# devBoard.net
KiCad netlist of a schematic drawn in EAGLE
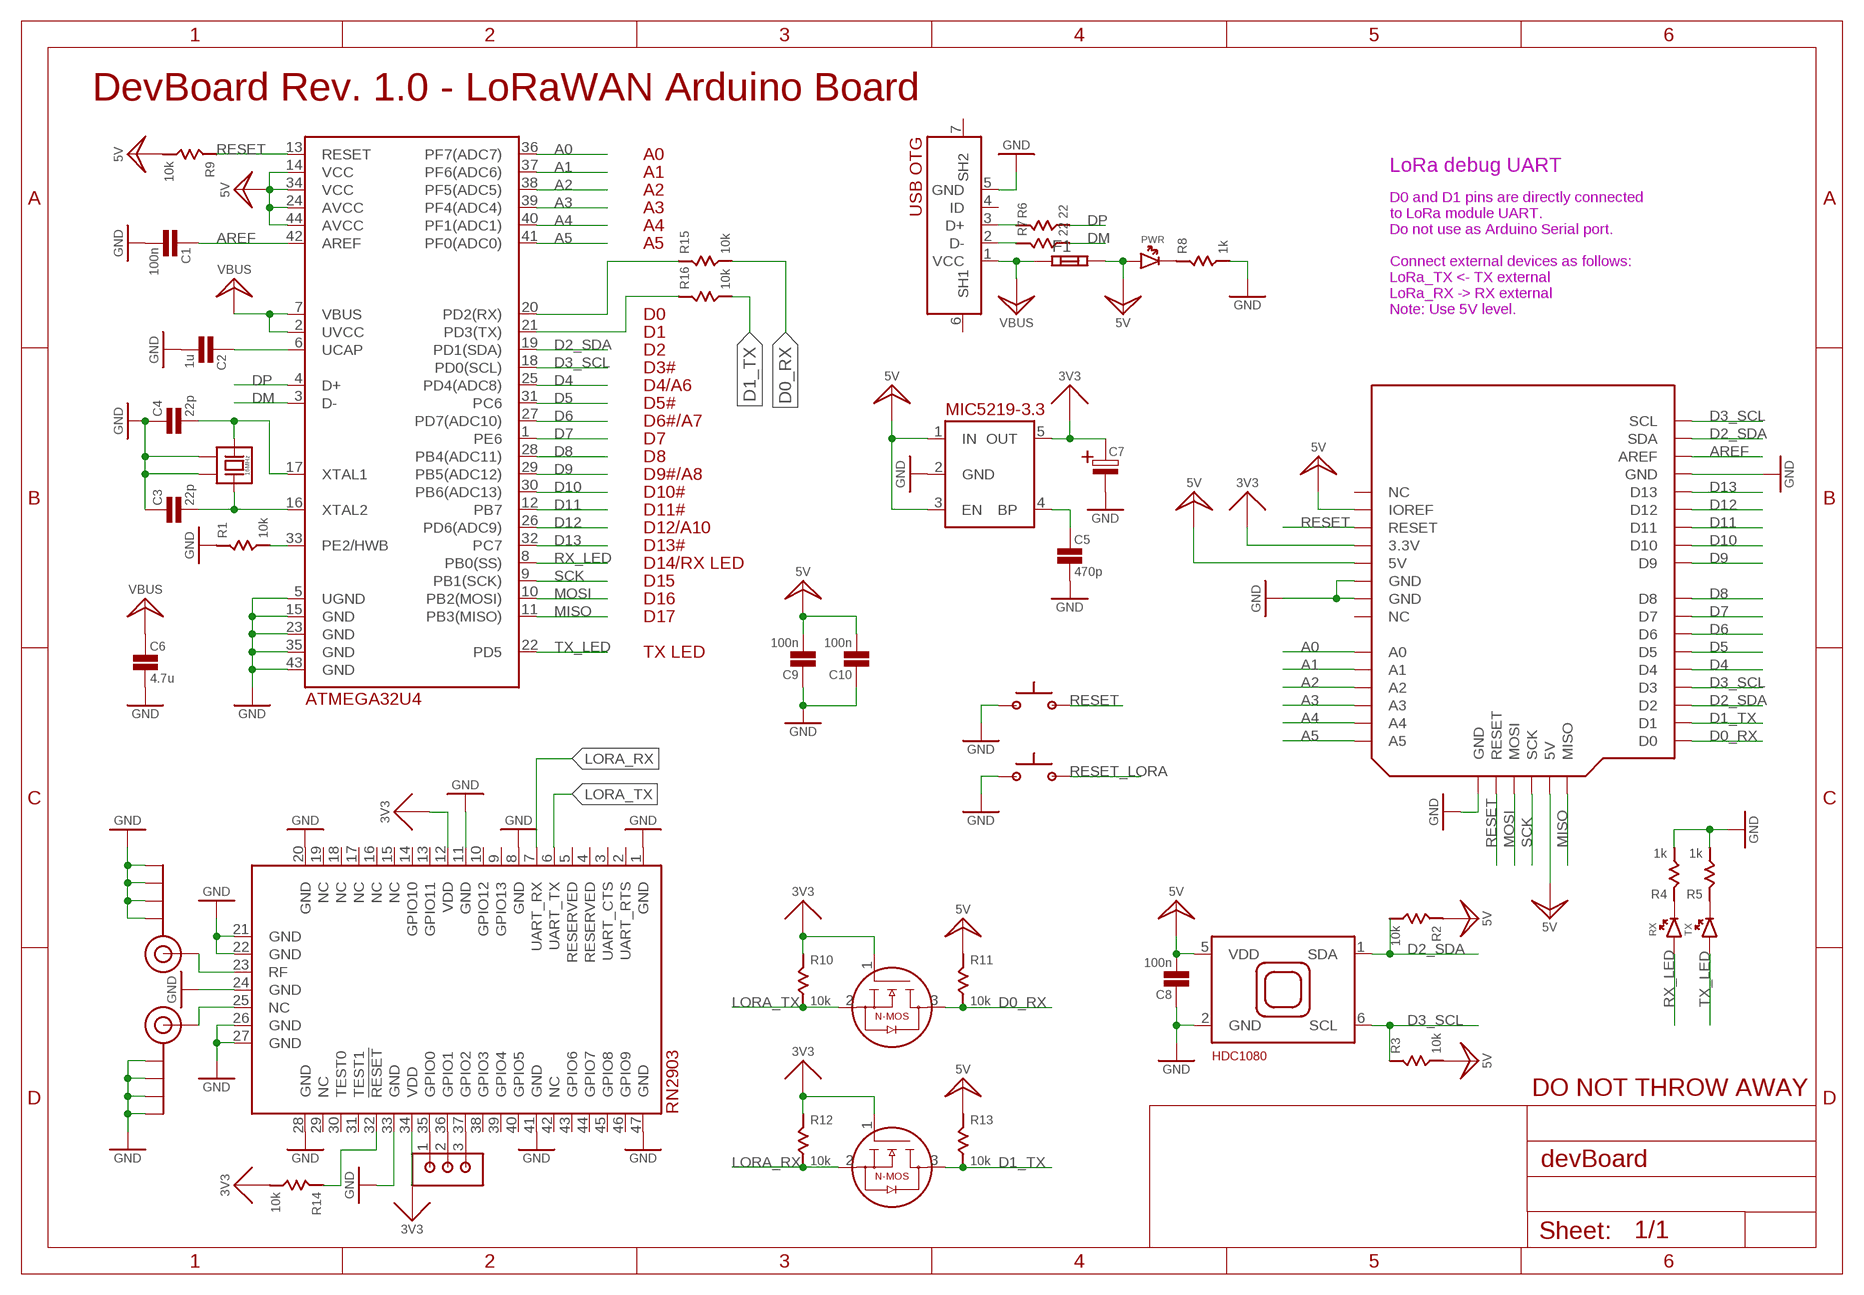
[diagram p0: schematic, sheet 1]

(export (version "E")
  (design (tool "Eeschema 10.0.6"))
  (components
    (comp (ref "C1")
      (value "100n")
      (footprint "eagle-import:0603")
      (libsource (lib "eagle-import") (part "C0603"))
    )
    (comp (ref "C2")
      (value "1u")
      (footprint "eagle-import:0603")
      (libsource (lib "eagle-import") (part "C0603"))
    )
    (comp (ref "C3")
      (value "22p")
      (footprint "eagle-import:0603")
      (libsource (lib "eagle-import") (part "C0603"))
    )
    (comp (ref "C4")
      (value "22p")
      (footprint "eagle-import:0603")
      (libsource (lib "eagle-import") (part "C0603"))
    )
    (comp (ref "C5")
      (value "470p")
      (footprint "eagle-import:0603")
      (libsource (lib "eagle-import") (part "C0603"))
    )
    (comp (ref "C6")
      (value "4.7u")
      (footprint "eagle-import:0603")
      (libsource (lib "eagle-import") (part "C0603"))
    )
    (comp (ref "C7")
      (value "CT3216")
      (footprint "eagle-import:CT3216")
      (libsource (lib "eagle-import") (part "CT3216"))
    )
    (comp (ref "C8")
      (value "100n")
      (footprint "eagle-import:0603")
      (libsource (lib "eagle-import") (part "C0603"))
    )
    (comp (ref "C9")
      (value "100n")
      (footprint "eagle-import:0603")
      (libsource (lib "eagle-import") (part "C0603"))
    )
    (comp (ref "C10")
      (value "100n")
      (footprint "eagle-import:0603")
      (libsource (lib "eagle-import") (part "C0603"))
    )
    (comp (ref "F1")
      (value "MF-MSMF050")
      (footprint "eagle-import:MF-MSMF050")
      (libsource (lib "eagle-import") (part "MF-MSMF050"))
    )
    (comp (ref "J$1")
      (value "SMA_EDGE")
      (footprint "eagle-import:SMA-EDGE")
      (libsource (lib "eagle-import") (part "SMA_EDGE"))
    )
    (comp (ref "J$2")
      (value "SMA_EDGE")
      (footprint "eagle-import:SMA-EDGE")
      (libsource (lib "eagle-import") (part "SMA_EDGE"))
    )
    (comp (ref "PWR")
      (value "PWR")
      (footprint "eagle-import:0603LED")
      (libsource (lib "eagle-import") (part "0603LED"))
    )
    (comp (ref "R1")
      (value "10k")
      (footprint "eagle-import:0603")
      (libsource (lib "eagle-import") (part "R0603"))
    )
    (comp (ref "R2")
      (value "10k")
      (footprint "eagle-import:0603")
      (libsource (lib "eagle-import") (part "R0603"))
    )
    (comp (ref "R3")
      (value "10k")
      (footprint "eagle-import:0603")
      (libsource (lib "eagle-import") (part "R0603"))
    )
    (comp (ref "R4")
      (value "1k")
      (footprint "eagle-import:0603")
      (libsource (lib "eagle-import") (part "R0603"))
    )
    (comp (ref "R5")
      (value "1k")
      (footprint "eagle-import:0603")
      (libsource (lib "eagle-import") (part "R0603"))
    )
    (comp (ref "R6")
      (value "22")
      (footprint "eagle-import:0603")
      (libsource (lib "eagle-import") (part "R0603"))
    )
    (comp (ref "R7")
      (value "22")
      (footprint "eagle-import:0603")
      (libsource (lib "eagle-import") (part "R0603"))
    )
    (comp (ref "R8")
      (value "1k")
      (footprint "eagle-import:0603")
      (libsource (lib "eagle-import") (part "R0603"))
    )
    (comp (ref "R9")
      (value "10k")
      (footprint "eagle-import:0603")
      (libsource (lib "eagle-import") (part "R0603"))
    )
    (comp (ref "R10")
      (value "10k")
      (footprint "eagle-import:0603")
      (libsource (lib "eagle-import") (part "R0603"))
    )
    (comp (ref "R11")
      (value "10k")
      (footprint "eagle-import:0603")
      (libsource (lib "eagle-import") (part "R0603"))
    )
    (comp (ref "R12")
      (value "10k")
      (footprint "eagle-import:0603")
      (libsource (lib "eagle-import") (part "R0603"))
    )
    (comp (ref "R13")
      (value "10k")
      (footprint "eagle-import:0603")
      (libsource (lib "eagle-import") (part "R0603"))
    )
    (comp (ref "R14")
      (value "10k")
      (footprint "eagle-import:0603")
      (libsource (lib "eagle-import") (part "R0603"))
    )
    (comp (ref "R15")
      (value "10k")
      (footprint "eagle-import:0603")
      (libsource (lib "eagle-import") (part "R0603"))
    )
    (comp (ref "R16")
      (value "10k")
      (footprint "eagle-import:0603")
      (libsource (lib "eagle-import") (part "R0603"))
    )
    (comp (ref "RX")
      (value "RX")
      (footprint "eagle-import:0603LED")
      (libsource (lib "eagle-import") (part "0603LED"))
    )
    (comp (ref "SW2")
      (value "PUSH_BTN")
      (footprint "eagle-import:PUSH_BTN")
      (libsource (lib "eagle-import") (part "PUSH_BTN"))
    )
    (comp (ref "SW3")
      (value "PUSH_BTN")
      (footprint "eagle-import:PUSH_BTN")
      (libsource (lib "eagle-import") (part "PUSH_BTN"))
    )
    (comp (ref "T1")
      (value "BSS138")
      (footprint "eagle-import:SOT23-3")
      (libsource (lib "eagle-import") (part "BSS138"))
    )
    (comp (ref "T2")
      (value "BSS138")
      (footprint "eagle-import:SOT23-3")
      (libsource (lib "eagle-import") (part "BSS138"))
    )
    (comp (ref "TX")
      (value "TX")
      (footprint "eagle-import:0603LED")
      (libsource (lib "eagle-import") (part "0603LED"))
    )
    (comp (ref "U$1")
      (value "ATMEGA32U4-MU")
      (footprint "eagle-import:QFN44")
      (libsource (lib "eagle-import") (part "ATMEGA32U4-MU"))
    )
    (comp (ref "U$2")
      (value "ARDUINO_UNO")
      (footprint "eagle-import:ARDUINO_UNO")
      (libsource (lib "eagle-import") (part "ARDUINO_UNO"))
    )
    (comp (ref "U$9")
      (value "HDC1080")
      (footprint "eagle-import:HDC1080")
      (libsource (lib "eagle-import") (part "HDC1080"))
    )
    (comp (ref "U$34")
      (value "MIC5219-3.3")
      (footprint "eagle-import:SOT-23-5")
      (libsource (lib "eagle-import") (part "MIC5219-3.3"))
    )
    (comp (ref "U$45")
      (value "USB_OTG")
      (footprint "eagle-import:USB_OTG")
      (libsource (lib "eagle-import") (part "USB_OTG"))
    )
    (comp (ref "U$59")
      (value "1X3_HEADER")
      (footprint "eagle-import:1X3_HEADER")
      (libsource (lib "eagle-import") (part "1X3_HEADER"))
    )
    (comp (ref "U$65")
      (value "DONT_THROW")
      (footprint "eagle-import:DONT_THROW")
      (libsource (lib "eagle-import") (part "DONT_THROW"))
    )
    (comp (ref "U1")
      (value "RN2903")
      (footprint "eagle-import:RN2903")
      (libsource (lib "eagle-import") (part "RN2903"))
    )
    (comp (ref "Y1")
      (value "16MHz")
      (footprint "eagle-import:XTAL3225")
      (libsource (lib "eagle-import") (part "CX3225SB12000H0PSTC1"))
    )
  )
  (nets
    (net (code "1") (name "/A0") (class "Default")
      (node (ref "U$1") (pin "36") (pinfunction "PF7(ADC7)_36") (pintype "bidirectional"))
      (node (ref "U$2") (pin "A0") (pinfunction "A0_A0") (pintype "bidirectional"))
    )
    (net (code "2") (name "/A1") (class "Default")
      (node (ref "U$1") (pin "37") (pinfunction "PF6(ADC6)_37") (pintype "bidirectional"))
      (node (ref "U$2") (pin "A1") (pinfunction "A1_A1") (pintype "bidirectional"))
    )
    (net (code "3") (name "/A2") (class "Default")
      (node (ref "U$1") (pin "38") (pinfunction "PF5(ADC5)_38") (pintype "bidirectional"))
      (node (ref "U$2") (pin "A2") (pinfunction "A2_A2") (pintype "bidirectional"))
    )
    (net (code "4") (name "/A3") (class "Default")
      (node (ref "U$1") (pin "39") (pinfunction "PF4(ADC4)_39") (pintype "bidirectional"))
      (node (ref "U$2") (pin "A3") (pinfunction "A3_A3") (pintype "bidirectional"))
    )
    (net (code "5") (name "/A4") (class "Default")
      (node (ref "U$1") (pin "40") (pinfunction "PF1(ADC1)_40") (pintype "bidirectional"))
      (node (ref "U$2") (pin "A4") (pinfunction "A4_A4") (pintype "bidirectional"))
    )
    (net (code "6") (name "/A5") (class "Default")
      (node (ref "U$1") (pin "41") (pinfunction "PF0(ADC0)_41") (pintype "bidirectional"))
      (node (ref "U$2") (pin "A5") (pinfunction "A5_A5") (pintype "bidirectional"))
    )
    (net (code "7") (name "/AREF") (class "Default")
      (node (ref "C1") (pin "1") (pinfunction "P$1_1") (pintype "bidirectional"))
      (node (ref "U$1") (pin "42") (pinfunction "AREF_42") (pintype "bidirectional"))
      (node (ref "U$2") (pin "AREF") (pinfunction "AREF_AREF") (pintype "bidirectional"))
    )
    (net (code "8") (name "/D2_SDA") (class "Default")
      (node (ref "R2") (pin "2") (pinfunction "P$2_2") (pintype "bidirectional"))
      (node (ref "U$1") (pin "19") (pinfunction "PD1(SDA)_19") (pintype "bidirectional"))
      (node (ref "U$2") (pin "D2") (pinfunction "D2_D2") (pintype "bidirectional"))
      (node (ref "U$2") (pin "SDA") (pinfunction "SDA_SDA") (pintype "bidirectional"))
      (node (ref "U$9") (pin "1") (pinfunction "SDA_1") (pintype "bidirectional"))
    )
    (net (code "9") (name "/D3_SCL") (class "Default")
      (node (ref "R3") (pin "1") (pinfunction "P$1_1") (pintype "bidirectional"))
      (node (ref "U$1") (pin "18") (pinfunction "PD0(SCL)_18") (pintype "bidirectional"))
      (node (ref "U$2") (pin "D3") (pinfunction "D3_D3") (pintype "bidirectional"))
      (node (ref "U$2") (pin "SCL") (pinfunction "SCL_SCL") (pintype "bidirectional"))
      (node (ref "U$9") (pin "6") (pinfunction "SCL_6") (pintype "bidirectional"))
    )
    (net (code "10") (name "/D4") (class "Default")
      (node (ref "U$1") (pin "25") (pinfunction "PD4(ADC8)_25") (pintype "bidirectional"))
      (node (ref "U$2") (pin "D4") (pinfunction "D4_D4") (pintype "bidirectional"))
    )
    (net (code "11") (name "/D5") (class "Default")
      (node (ref "U$1") (pin "31") (pinfunction "PC6_31") (pintype "bidirectional"))
      (node (ref "U$2") (pin "D5") (pinfunction "D5_D5") (pintype "bidirectional"))
    )
    (net (code "12") (name "/D6") (class "Default")
      (node (ref "U$1") (pin "27") (pinfunction "PD7(ADC10)_27") (pintype "bidirectional"))
      (node (ref "U$2") (pin "D6") (pinfunction "D6_D6") (pintype "bidirectional"))
    )
    (net (code "13") (name "/D7") (class "Default")
      (node (ref "U$1") (pin "1") (pinfunction "PE6_1") (pintype "bidirectional"))
      (node (ref "U$2") (pin "D7") (pinfunction "D7_D7") (pintype "bidirectional"))
    )
    (net (code "14") (name "/D8") (class "Default")
      (node (ref "U$1") (pin "28") (pinfunction "PB4(ADC11)_28") (pintype "bidirectional"))
      (node (ref "U$2") (pin "D8") (pinfunction "D8_D8") (pintype "bidirectional"))
    )
    (net (code "15") (name "/D9") (class "Default")
      (node (ref "U$1") (pin "29") (pinfunction "PB5(ADC12)_29") (pintype "bidirectional"))
      (node (ref "U$2") (pin "D9") (pinfunction "D9_D9") (pintype "bidirectional"))
    )
    (net (code "16") (name "/D10") (class "Default")
      (node (ref "U$1") (pin "30") (pinfunction "PB6(ADC13)_30") (pintype "bidirectional"))
      (node (ref "U$2") (pin "D10") (pinfunction "D10_D10") (pintype "bidirectional"))
    )
    (net (code "17") (name "/D11") (class "Default")
      (node (ref "U$1") (pin "12") (pinfunction "PB7_12") (pintype "bidirectional"))
      (node (ref "U$2") (pin "D11") (pinfunction "D11_D11") (pintype "bidirectional"))
    )
    (net (code "18") (name "/D12") (class "Default")
      (node (ref "U$1") (pin "26") (pinfunction "PD6(ADC9)_26") (pintype "bidirectional"))
      (node (ref "U$2") (pin "D12") (pinfunction "D12_D12") (pintype "bidirectional"))
    )
    (net (code "19") (name "/D13") (class "Default")
      (node (ref "U$1") (pin "32") (pinfunction "PC7_32") (pintype "bidirectional"))
      (node (ref "U$2") (pin "D13") (pinfunction "D13_D13") (pintype "bidirectional"))
    )
    (net (code "20") (name "/DM") (class "Default")
      (node (ref "R7") (pin "2") (pinfunction "P$2_2") (pintype "bidirectional"))
      (node (ref "U$1") (pin "3") (pinfunction "D-_3") (pintype "bidirectional"))
    )
    (net (code "21") (name "/DP") (class "Default")
      (node (ref "R6") (pin "2") (pinfunction "P$2_2") (pintype "bidirectional"))
      (node (ref "U$1") (pin "4") (pinfunction "D+_4") (pintype "bidirectional"))
    )
    (net (code "22") (name "/MISO") (class "Default")
      (node (ref "U$1") (pin "11") (pinfunction "PB3(MISO)_11") (pintype "bidirectional"))
      (node (ref "U$2") (pin "ICSP_1") (pinfunction "MISO_ICSP_1") (pintype "bidirectional"))
    )
    (net (code "23") (name "/MOSI") (class "Default")
      (node (ref "U$1") (pin "10") (pinfunction "PB2(MOSI)_10") (pintype "bidirectional"))
      (node (ref "U$2") (pin "ICSP_4") (pinfunction "MOSI_ICSP_4") (pintype "bidirectional"))
    )
    (net (code "24") (name "/RESET") (class "Default")
      (node (ref "R9") (pin "1") (pinfunction "P$1_1") (pintype "bidirectional"))
      (node (ref "SW2") (pin "2") (pinfunction "2_2") (pintype "bidirectional"))
      (node (ref "U$1") (pin "13") (pinfunction "RESET_13") (pintype "bidirectional"))
      (node (ref "U$2") (pin "ICSP_5") (pinfunction "RESET_ICSP_5") (pintype "bidirectional"))
      (node (ref "U$2") (pin "RESET") (pinfunction "RESET_RESET") (pintype "bidirectional"))
    )
    (net (code "25") (name "/RESET_LORA") (class "Default")
      (node (ref "R14") (pin "1") (pinfunction "P$1_1") (pintype "bidirectional"))
      (node (ref "SW3") (pin "2") (pinfunction "2_2") (pintype "bidirectional"))
      (node (ref "U1") (pin "32") (pinfunction "~{RESET}_32") (pintype "bidirectional"))
    )
    (net (code "26") (name "/RX_LED") (class "Default")
      (node (ref "RX") (pin "AN") (pinfunction "AN_AN") (pintype "bidirectional"))
      (node (ref "U$1") (pin "8") (pinfunction "PB0(SS)_8") (pintype "bidirectional"))
    )
    (net (code "27") (name "/SCK") (class "Default")
      (node (ref "U$1") (pin "9") (pinfunction "PB1(SCK)_9") (pintype "bidirectional"))
      (node (ref "U$2") (pin "ICSP_3") (pinfunction "SCK_ICSP_3") (pintype "bidirectional"))
    )
    (net (code "28") (name "/TX_LED") (class "Default")
      (node (ref "TX") (pin "AN") (pinfunction "AN_AN") (pintype "bidirectional"))
      (node (ref "U$1") (pin "22") (pinfunction "PD5_22") (pintype "bidirectional"))
    )
    (net (code "29") (name "3V3") (class "Default")
      (node (ref "C7") (pin "AN") (pinfunction "AN_AN") (pintype "bidirectional"))
      (node (ref "R10") (pin "1") (pinfunction "P$1_1") (pintype "bidirectional"))
      (node (ref "R12") (pin "1") (pinfunction "P$1_1") (pintype "bidirectional"))
      (node (ref "R14") (pin "2") (pinfunction "P$2_2") (pintype "bidirectional"))
      (node (ref "T1") (pin "1") (pinfunction "G_1") (pintype "bidirectional"))
      (node (ref "T2") (pin "1") (pinfunction "G_1") (pintype "bidirectional"))
      (node (ref "U$2") (pin "3.3V") (pinfunction "3.3V_3.3V") (pintype "bidirectional"))
      (node (ref "U$34") (pin "5") (pinfunction "OUT_5") (pintype "bidirectional"))
      (node (ref "U1") (pin "12") (pinfunction "VDD_12") (pintype "bidirectional"))
      (node (ref "U1") (pin "34") (pinfunction "VDD_34") (pintype "bidirectional"))
    )
    (net (code "30") (name "5V") (class "Default")
      (node (ref "C10") (pin "2") (pinfunction "P$2_2") (pintype "bidirectional"))
      (node (ref "C8") (pin "2") (pinfunction "P$2_2") (pintype "bidirectional"))
      (node (ref "C9") (pin "2") (pinfunction "P$2_2") (pintype "bidirectional"))
      (node (ref "F1") (pin "2") (pinfunction "P$2_2") (pintype "bidirectional"))
      (node (ref "PWR") (pin "AN") (pinfunction "AN_AN") (pintype "bidirectional"))
      (node (ref "R11") (pin "1") (pinfunction "P$1_1") (pintype "bidirectional"))
      (node (ref "R13") (pin "1") (pinfunction "P$1_1") (pintype "bidirectional"))
      (node (ref "R2") (pin "1") (pinfunction "P$1_1") (pintype "bidirectional"))
      (node (ref "R3") (pin "2") (pinfunction "P$2_2") (pintype "bidirectional"))
      (node (ref "R9") (pin "2") (pinfunction "P$2_2") (pintype "bidirectional"))
      (node (ref "U$1") (pin "14") (pinfunction "VCC_14") (pintype "bidirectional"))
      (node (ref "U$1") (pin "24") (pinfunction "AVCC_24") (pintype "bidirectional"))
      (node (ref "U$1") (pin "34") (pinfunction "VCC_34") (pintype "bidirectional"))
      (node (ref "U$1") (pin "44") (pinfunction "AVCC_44") (pintype "bidirectional"))
      (node (ref "U$2") (pin "5V") (pinfunction "5V_5V") (pintype "bidirectional"))
      (node (ref "U$2") (pin "ICSP_2") (pinfunction "5V_ICSP_2") (pintype "bidirectional"))
      (node (ref "U$2") (pin "IOREF") (pinfunction "IOREF_IOREF") (pintype "bidirectional"))
      (node (ref "U$34") (pin "1") (pinfunction "IN_1") (pintype "bidirectional"))
      (node (ref "U$34") (pin "3") (pinfunction "EN_3") (pintype "bidirectional"))
      (node (ref "U$9") (pin "5") (pinfunction "VDD_5") (pintype "bidirectional"))
    )
    (net (code "31") (name "D0_RX") (class "Default")
      (node (ref "R11") (pin "2") (pinfunction "P$2_2") (pintype "bidirectional"))
      (node (ref "R15") (pin "2") (pinfunction "P$2_2") (pintype "bidirectional"))
      (node (ref "T1") (pin "3") (pinfunction "D_3") (pintype "bidirectional"))
      (node (ref "U$2") (pin "D0") (pinfunction "D0_D0") (pintype "bidirectional"))
    )
    (net (code "32") (name "D1_TX") (class "Default")
      (node (ref "R13") (pin "2") (pinfunction "P$2_2") (pintype "bidirectional"))
      (node (ref "R16") (pin "2") (pinfunction "P$2_2") (pintype "bidirectional"))
      (node (ref "T2") (pin "3") (pinfunction "D_3") (pintype "bidirectional"))
      (node (ref "U$2") (pin "D1") (pinfunction "D1_D1") (pintype "bidirectional"))
    )
    (net (code "33") (name "GND") (class "Default")
      (node (ref "C1") (pin "2") (pinfunction "P$2_2") (pintype "bidirectional"))
      (node (ref "C10") (pin "1") (pinfunction "P$1_1") (pintype "bidirectional"))
      (node (ref "C2") (pin "2") (pinfunction "P$2_2") (pintype "bidirectional"))
      (node (ref "C3") (pin "1") (pinfunction "P$1_1") (pintype "bidirectional"))
      (node (ref "C4") (pin "1") (pinfunction "P$1_1") (pintype "bidirectional"))
      (node (ref "C5") (pin "2") (pinfunction "P$2_2") (pintype "bidirectional"))
      (node (ref "C6") (pin "2") (pinfunction "P$2_2") (pintype "bidirectional"))
      (node (ref "C7") (pin "CAT") (pinfunction "CAT_CAT") (pintype "bidirectional"))
      (node (ref "C8") (pin "1") (pinfunction "P$1_1") (pintype "bidirectional"))
      (node (ref "C9") (pin "1") (pinfunction "P$1_1") (pintype "bidirectional"))
      (node (ref "J$1") (pin "GND@0") (pinfunction "GND_GND@0") (pintype "bidirectional"))
      (node (ref "J$1") (pin "GND@1") (pinfunction "GND_GND@1") (pintype "bidirectional"))
      (node (ref "J$1") (pin "GND@2") (pinfunction "GND_GND@2") (pintype "bidirectional"))
      (node (ref "J$1") (pin "GND@3") (pinfunction "GND_GND@3") (pintype "bidirectional"))
      (node (ref "J$2") (pin "GND@0") (pinfunction "GND_GND@0") (pintype "bidirectional"))
      (node (ref "J$2") (pin "GND@1") (pinfunction "GND_GND@1") (pintype "bidirectional"))
      (node (ref "J$2") (pin "GND@2") (pinfunction "GND_GND@2") (pintype "bidirectional"))
      (node (ref "J$2") (pin "GND@3") (pinfunction "GND_GND@3") (pintype "bidirectional"))
      (node (ref "R1") (pin "1") (pinfunction "P$1_1") (pintype "bidirectional"))
      (node (ref "R4") (pin "2") (pinfunction "P$2_2") (pintype "bidirectional"))
      (node (ref "R5") (pin "2") (pinfunction "P$2_2") (pintype "bidirectional"))
      (node (ref "R8") (pin "2") (pinfunction "P$2_2") (pintype "bidirectional"))
      (node (ref "SW2") (pin "1") (pinfunction "1_1") (pintype "bidirectional"))
      (node (ref "SW3") (pin "1") (pinfunction "1_1") (pintype "bidirectional"))
      (node (ref "U$1") (pin "15") (pinfunction "GND_15") (pintype "bidirectional"))
      (node (ref "U$1") (pin "23") (pinfunction "GND_23") (pintype "bidirectional"))
      (node (ref "U$1") (pin "35") (pinfunction "GND_35") (pintype "bidirectional"))
      (node (ref "U$1") (pin "43") (pinfunction "GND_43") (pintype "bidirectional"))
      (node (ref "U$1") (pin "5") (pinfunction "UGND_5") (pintype "bidirectional"))
      (node (ref "U$2") (pin "GND@2") (pinfunction "GND_GND@2") (pintype "bidirectional"))
      (node (ref "U$2") (pin "GND@3") (pinfunction "GND_GND@3") (pintype "bidirectional"))
      (node (ref "U$2") (pin "GND@4") (pinfunction "GND_GND@4") (pintype "bidirectional"))
      (node (ref "U$2") (pin "ICSP_6") (pinfunction "GND_ICSP_6") (pintype "bidirectional"))
      (node (ref "U$34") (pin "2") (pinfunction "GND_2") (pintype "bidirectional"))
      (node (ref "U$45") (pin "5") (pinfunction "GND_5") (pintype "bidirectional"))
      (node (ref "U$9") (pin "2") (pinfunction "GND_2") (pintype "bidirectional"))
      (node (ref "U1") (pin "1") (pinfunction "GND_1") (pintype "bidirectional"))
      (node (ref "U1") (pin "11") (pinfunction "GND_11") (pintype "bidirectional"))
      (node (ref "U1") (pin "20") (pinfunction "GND_20") (pintype "bidirectional"))
      (node (ref "U1") (pin "21") (pinfunction "GND_21") (pintype "bidirectional"))
      (node (ref "U1") (pin "22") (pinfunction "GND_22") (pintype "bidirectional"))
      (node (ref "U1") (pin "24") (pinfunction "GND_24") (pintype "bidirectional"))
      (node (ref "U1") (pin "26") (pinfunction "GND_26") (pintype "bidirectional"))
      (node (ref "U1") (pin "27") (pinfunction "GND_27") (pintype "bidirectional"))
      (node (ref "U1") (pin "28") (pinfunction "GND_28") (pintype "bidirectional"))
      (node (ref "U1") (pin "33") (pinfunction "GND_33") (pintype "bidirectional"))
      (node (ref "U1") (pin "41") (pinfunction "GND_41") (pintype "bidirectional"))
      (node (ref "U1") (pin "47") (pinfunction "GND_47") (pintype "bidirectional"))
      (node (ref "U1") (pin "8") (pinfunction "GND_8") (pintype "bidirectional"))
      (node (ref "Y1") (pin "2") (pinfunction "2_2") (pintype "bidirectional"))
      (node (ref "Y1") (pin "4") (pinfunction "4_4") (pintype "bidirectional"))
    )
    (net (code "34") (name "LORA_RX") (class "Default")
      (node (ref "R12") (pin "2") (pinfunction "P$2_2") (pintype "bidirectional"))
      (node (ref "T2") (pin "2") (pinfunction "S_2") (pintype "bidirectional"))
      (node (ref "U1") (pin "7") (pinfunction "UART_RX_7") (pintype "bidirectional"))
    )
    (net (code "35") (name "LORA_TX") (class "Default")
      (node (ref "R10") (pin "2") (pinfunction "P$2_2") (pintype "bidirectional"))
      (node (ref "T1") (pin "2") (pinfunction "S_2") (pintype "bidirectional"))
      (node (ref "U1") (pin "6") (pinfunction "UART_TX_6") (pintype "bidirectional"))
    )
    (net (code "36") (name "Net-(C2-P$1)") (class "Default")
      (node (ref "C2") (pin "1") (pinfunction "P$1_1") (pintype "bidirectional"))
      (node (ref "U$1") (pin "6") (pinfunction "UCAP_6") (pintype "bidirectional"))
    )
    (net (code "37") (name "Net-(C3-P$2)") (class "Default")
      (node (ref "C3") (pin "2") (pinfunction "P$2_2") (pintype "bidirectional"))
      (node (ref "U$1") (pin "16") (pinfunction "XTAL2_16") (pintype "bidirectional"))
      (node (ref "Y1") (pin "1") (pinfunction "1_1") (pintype "bidirectional"))
    )
    (net (code "38") (name "Net-(C4-P$2)") (class "Default")
      (node (ref "C4") (pin "2") (pinfunction "P$2_2") (pintype "bidirectional"))
      (node (ref "U$1") (pin "17") (pinfunction "XTAL1_17") (pintype "bidirectional"))
      (node (ref "Y1") (pin "3") (pinfunction "3_3") (pintype "bidirectional"))
    )
    (net (code "39") (name "Net-(C5-P$1)") (class "Default")
      (node (ref "C5") (pin "1") (pinfunction "P$1_1") (pintype "bidirectional"))
      (node (ref "U$34") (pin "4") (pinfunction "BP_4") (pintype "bidirectional"))
    )
    (net (code "40") (name "Net-(J$1-SIGNAL)") (class "Default")
      (node (ref "J$1") (pin "SIG") (pinfunction "SIGNAL_SIG") (pintype "bidirectional"))
      (node (ref "U1") (pin "23") (pinfunction "RF_23") (pintype "bidirectional"))
    )
    (net (code "41") (name "Net-(J$2-SIGNAL)") (class "Default")
      (node (ref "J$2") (pin "SIG") (pinfunction "SIGNAL_SIG") (pintype "bidirectional"))
      (node (ref "U1") (pin "25") (pinfunction "NC_25") (pintype "bidirectional"))
    )
    (net (code "42") (name "Net-(R1-P$2)") (class "Default")
      (node (ref "R1") (pin "2") (pinfunction "P$2_2") (pintype "bidirectional"))
      (node (ref "U$1") (pin "33") (pinfunction "PE2/HWB_33") (pintype "bidirectional"))
    )
    (net (code "43") (name "Net-(R4-P$1)") (class "Default")
      (node (ref "R4") (pin "1") (pinfunction "P$1_1") (pintype "bidirectional"))
      (node (ref "RX") (pin "CA") (pinfunction "CA_CA") (pintype "bidirectional"))
    )
    (net (code "44") (name "Net-(R5-P$1)") (class "Default")
      (node (ref "R5") (pin "1") (pinfunction "P$1_1") (pintype "bidirectional"))
      (node (ref "TX") (pin "CA") (pinfunction "CA_CA") (pintype "bidirectional"))
    )
    (net (code "45") (name "Net-(R6-P$1)") (class "Default")
      (node (ref "R6") (pin "1") (pinfunction "P$1_1") (pintype "bidirectional"))
      (node (ref "U$45") (pin "3") (pinfunction "D+_3") (pintype "bidirectional"))
    )
    (net (code "46") (name "Net-(R7-P$1)") (class "Default")
      (node (ref "R7") (pin "1") (pinfunction "P$1_1") (pintype "bidirectional"))
      (node (ref "U$45") (pin "2") (pinfunction "D-_2") (pintype "bidirectional"))
    )
    (net (code "47") (name "Net-(R8-P$1)") (class "Default")
      (node (ref "PWR") (pin "CA") (pinfunction "CA_CA") (pintype "bidirectional"))
      (node (ref "R8") (pin "1") (pinfunction "P$1_1") (pintype "bidirectional"))
    )
    (net (code "48") (name "Net-(R15-P$1)") (class "Default")
      (node (ref "R15") (pin "1") (pinfunction "P$1_1") (pintype "bidirectional"))
      (node (ref "U$1") (pin "20") (pinfunction "PD2(RX)_20") (pintype "bidirectional"))
    )
    (net (code "49") (name "Net-(R16-P$1)") (class "Default")
      (node (ref "R16") (pin "1") (pinfunction "P$1_1") (pintype "bidirectional"))
      (node (ref "U$1") (pin "21") (pinfunction "PD3(TX)_21") (pintype "bidirectional"))
    )
    (net (code "50") (name "Net-(U1-GPIO0)") (class "Default")
      (node (ref "U$59") (pin "1") (pinfunction "1_1") (pintype "bidirectional"))
      (node (ref "U1") (pin "35") (pinfunction "GPIO0_35") (pintype "bidirectional"))
    )
    (net (code "51") (name "Net-(U1-GPIO1)") (class "Default")
      (node (ref "U$59") (pin "2") (pinfunction "2_2") (pintype "bidirectional"))
      (node (ref "U1") (pin "36") (pinfunction "GPIO1_36") (pintype "bidirectional"))
    )
    (net (code "52") (name "Net-(U1-GPIO2)") (class "Default")
      (node (ref "U$59") (pin "3") (pinfunction "3_3") (pintype "bidirectional"))
      (node (ref "U1") (pin "37") (pinfunction "GPIO2_37") (pintype "bidirectional"))
    )
    (net (code "53") (name "VBUS") (class "Default")
      (node (ref "C6") (pin "1") (pinfunction "P$1_1") (pintype "bidirectional"))
      (node (ref "F1") (pin "1") (pinfunction "P$1_1") (pintype "bidirectional"))
      (node (ref "U$1") (pin "2") (pinfunction "UVCC_2") (pintype "bidirectional"))
      (node (ref "U$1") (pin "7") (pinfunction "VBUS_7") (pintype "bidirectional"))
      (node (ref "U$45") (pin "1") (pinfunction "VCC_1") (pintype "bidirectional"))
    )
    (net (code "54") (name "unconnected-(U$2-NC-PadNC@1)") (class "Default")
      (node (ref "U$2") (pin "NC@1") (pinfunction "NC_NC@1") (pintype "bidirectional"))
    )
    (net (code "55") (name "unconnected-(U$2-NC-PadNC@2)") (class "Default")
      (node (ref "U$2") (pin "NC@2") (pinfunction "NC_NC@2") (pintype "bidirectional"))
    )
    (net (code "56") (name "unconnected-(U$45-ID-Pad4)") (class "Default")
      (node (ref "U$45") (pin "4") (pinfunction "ID_4") (pintype "bidirectional"))
    )
    (net (code "57") (name "unconnected-(U$45-SH1-Pad6)") (class "Default")
      (node (ref "U$45") (pin "6") (pinfunction "SH1_6") (pintype "bidirectional"))
    )
    (net (code "58") (name "unconnected-(U$45-SH2-Pad7)") (class "Default")
      (node (ref "U$45") (pin "7") (pinfunction "SH2_7") (pintype "bidirectional"))
    )
    (net (code "59") (name "unconnected-(U1-GPIO3-Pad38)") (class "Default")
      (node (ref "U1") (pin "38") (pinfunction "GPIO3_38") (pintype "bidirectional"))
    )
    (net (code "60") (name "unconnected-(U1-GPIO4-Pad39)") (class "Default")
      (node (ref "U1") (pin "39") (pinfunction "GPIO4_39") (pintype "bidirectional"))
    )
    (net (code "61") (name "unconnected-(U1-GPIO5-Pad40)") (class "Default")
      (node (ref "U1") (pin "40") (pinfunction "GPIO5_40") (pintype "bidirectional"))
    )
    (net (code "62") (name "unconnected-(U1-GPIO6-Pad43)") (class "Default")
      (node (ref "U1") (pin "43") (pinfunction "GPIO6_43") (pintype "bidirectional"))
    )
    (net (code "63") (name "unconnected-(U1-GPIO7-Pad44)") (class "Default")
      (node (ref "U1") (pin "44") (pinfunction "GPIO7_44") (pintype "bidirectional"))
    )
    (net (code "64") (name "unconnected-(U1-GPIO8-Pad45)") (class "Default")
      (node (ref "U1") (pin "45") (pinfunction "GPIO8_45") (pintype "bidirectional"))
    )
    (net (code "65") (name "unconnected-(U1-GPIO9-Pad46)") (class "Default")
      (node (ref "U1") (pin "46") (pinfunction "GPIO9_46") (pintype "bidirectional"))
    )
    (net (code "66") (name "unconnected-(U1-GPIO10-Pad14)") (class "Default")
      (node (ref "U1") (pin "14") (pinfunction "GPIO10_14") (pintype "bidirectional"))
    )
    (net (code "67") (name "unconnected-(U1-GPIO11-Pad13)") (class "Default")
      (node (ref "U1") (pin "13") (pinfunction "GPIO11_13") (pintype "bidirectional"))
    )
    (net (code "68") (name "unconnected-(U1-GPIO12-Pad10)") (class "Default")
      (node (ref "U1") (pin "10") (pinfunction "GPIO12_10") (pintype "bidirectional"))
    )
    (net (code "69") (name "unconnected-(U1-GPIO13-Pad9)") (class "Default")
      (node (ref "U1") (pin "9") (pinfunction "GPIO13_9") (pintype "bidirectional"))
    )
    (net (code "70") (name "unconnected-(U1-NC-Pad15)") (class "Default")
      (node (ref "U1") (pin "15") (pinfunction "NC_15") (pintype "bidirectional"))
    )
    (net (code "71") (name "unconnected-(U1-NC-Pad16)") (class "Default")
      (node (ref "U1") (pin "16") (pinfunction "NC_16") (pintype "bidirectional"))
    )
    (net (code "72") (name "unconnected-(U1-NC-Pad17)") (class "Default")
      (node (ref "U1") (pin "17") (pinfunction "NC_17") (pintype "bidirectional"))
    )
    (net (code "73") (name "unconnected-(U1-NC-Pad18)") (class "Default")
      (node (ref "U1") (pin "18") (pinfunction "NC_18") (pintype "bidirectional"))
    )
    (net (code "74") (name "unconnected-(U1-NC-Pad19)") (class "Default")
      (node (ref "U1") (pin "19") (pinfunction "NC_19") (pintype "bidirectional"))
    )
    (net (code "75") (name "unconnected-(U1-NC-Pad29)") (class "Default")
      (node (ref "U1") (pin "29") (pinfunction "NC_29") (pintype "bidirectional"))
    )
    (net (code "76") (name "unconnected-(U1-NC-Pad42)") (class "Default")
      (node (ref "U1") (pin "42") (pinfunction "NC_42") (pintype "bidirectional"))
    )
    (net (code "77") (name "unconnected-(U1-RESERVED-Pad4)") (class "Default")
      (node (ref "U1") (pin "4") (pinfunction "RESERVED_4") (pintype "bidirectional"))
    )
    (net (code "78") (name "unconnected-(U1-RESERVED-Pad5)") (class "Default")
      (node (ref "U1") (pin "5") (pinfunction "RESERVED_5") (pintype "bidirectional"))
    )
    (net (code "79") (name "unconnected-(U1-TEST0-Pad30)") (class "Default")
      (node (ref "U1") (pin "30") (pinfunction "TEST0_30") (pintype "bidirectional"))
    )
    (net (code "80") (name "unconnected-(U1-TEST1-Pad31)") (class "Default")
      (node (ref "U1") (pin "31") (pinfunction "TEST1_31") (pintype "bidirectional"))
    )
    (net (code "81") (name "unconnected-(U1-UART_CTS-Pad3)") (class "Default")
      (node (ref "U1") (pin "3") (pinfunction "UART_CTS_3") (pintype "bidirectional"))
    )
    (net (code "82") (name "unconnected-(U1-UART_RTS-Pad2)") (class "Default")
      (node (ref "U1") (pin "2") (pinfunction "UART_RTS_2") (pintype "bidirectional"))
    )
  )
)
